# DP-logic.net
KiCad netlist of a schematic drawn in EAGLE
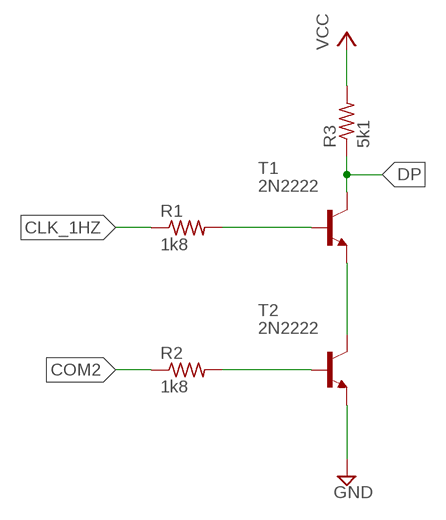
[diagram p0: schematic, sheet 1]

(export (version "E")
  (design (tool "Eeschema 10.0.6"))
  (components
    (comp (ref "R1")
      (value "1k8")
      (footprint "eagle-import:0204_7")
      (libsource (lib "eagle-import") (part "R-US_0204/7"))
    )
    (comp (ref "R2")
      (value "1k8")
      (footprint "eagle-import:0204_7")
      (libsource (lib "eagle-import") (part "R-US_0204/7"))
    )
    (comp (ref "R3")
      (value "5k1")
      (footprint "eagle-import:0204_7")
      (libsource (lib "eagle-import") (part "R-US_0204/7"))
    )
    (comp (ref "T1")
      (value "2N2222")
      (footprint "eagle-import:TO92-EBC-OVAL")
      (libsource (lib "eagle-import") (part "2N2222"))
    )
    (comp (ref "T2")
      (value "2N2222")
      (footprint "eagle-import:TO92-EBC-OVAL")
      (libsource (lib "eagle-import") (part "2N2222"))
    )
  )
  (nets
    (net (code "1") (name "CLK_1HZ") (class "Default")
      (node (ref "R1") (pin "1") (pinfunction "1_1") (pintype "passive"))
    )
    (net (code "2") (name "COM2") (class "Default")
      (node (ref "R2") (pin "1") (pinfunction "1_1") (pintype "passive"))
    )
    (net (code "3") (name "DP") (class "Default")
      (node (ref "R3") (pin "1") (pinfunction "1_1") (pintype "passive"))
      (node (ref "T1") (pin "C") (pinfunction "C_C") (pintype "passive"))
    )
    (net (code "4") (name "GND") (class "Default")
      (node (ref "T2") (pin "E") (pinfunction "E_E") (pintype "passive"))
    )
    (net (code "5") (name "Net-(R1-Pad2)") (class "Default")
      (node (ref "R1") (pin "2") (pinfunction "2_2") (pintype "passive"))
      (node (ref "T1") (pin "B") (pinfunction "B_B") (pintype "passive"))
    )
    (net (code "6") (name "Net-(R2-Pad2)") (class "Default")
      (node (ref "R2") (pin "2") (pinfunction "2_2") (pintype "passive"))
      (node (ref "T2") (pin "B") (pinfunction "B_B") (pintype "passive"))
    )
    (net (code "7") (name "Net-(T1-PadE)") (class "Default")
      (node (ref "T1") (pin "E") (pinfunction "E_E") (pintype "passive"))
      (node (ref "T2") (pin "C") (pinfunction "C_C") (pintype "passive"))
    )
    (net (code "8") (name "VCC") (class "Default")
      (node (ref "R3") (pin "2") (pinfunction "2_2") (pintype "passive"))
    )
  )
)
